# LPEDT_revA1_bikeit_GPS.net
KiCad netlist of a schematic drawn in Altium Designer
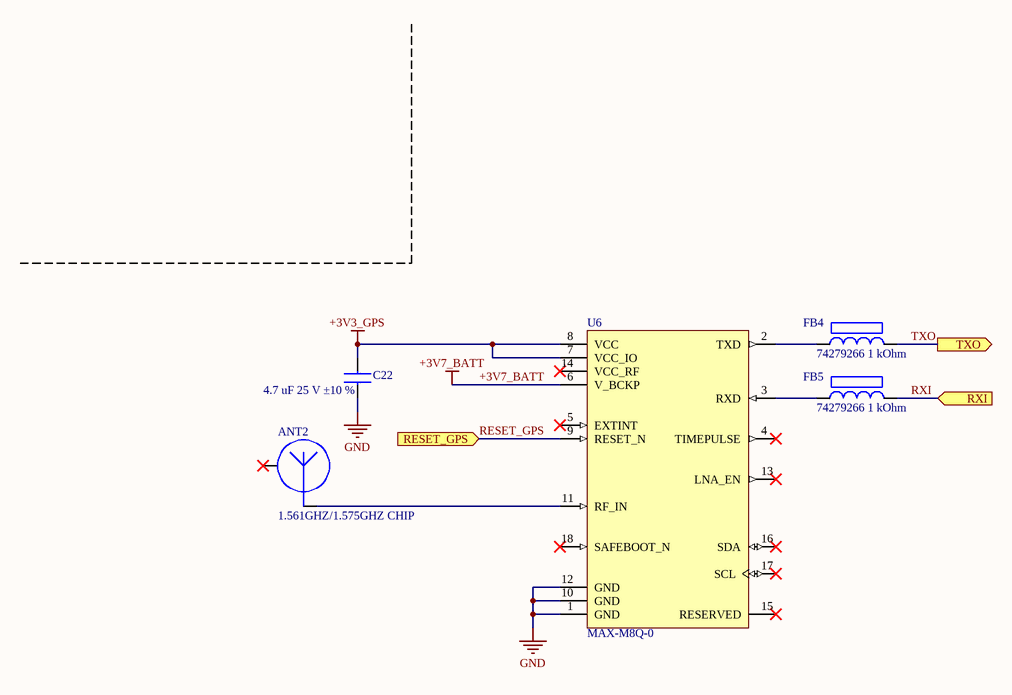
[diagram p0: LPEDT_revA1_bikeit_GPS.SchDoc]

(export (version "E")
  (design (tool "Eeschema 10.0.6"))
  (components
    (comp (ref "ANT2")
      (value "1.561GHZ/1.575GHZ CHIP")
      (description "RF ANT 1.561GHZ/1.575GHZ CHIP")
      (fields
        (field (name "MANUFACTURER") "Johanson")
        (field (name "MANUFACTURER PART NUMBER") "1575AT43A0040E")
      )
      (libsource (lib "LPEDT_revA1_bikeit_IL") (part "1575AT43A0040E"))
    )
    (comp (ref "C22")
      (value "4.7 uF 25 V ±10 %")
      (footprint "CAP_0603_1.60mm*0.80mm")
      (description "Cap Ceramic 0603 4.7 uF 25 V ±10 % Tolerance X5R SMT Multilayer Ceramic Capacitor")
      (fields
        (field (name "MANUFACTURER") "Murata")
        (field (name "MANUFACTURER PART NUMBER") "GRM188R61E475KE11D")
      )
      (libsource (lib "LPEDT_revA1_bikeit_IL") (part "GRM188R61E475KE11D"))
    )
    (comp (ref "FB4")
      (value "74279266 1 kOhm")
      (footprint "FB_0603_1.60mm*0.80mm")
      (description "Ferrite Bead, 0603 [1608 Metric], 1 kohm, 200 mA, WE-CBF Series, 0.6 ohm, ± 25%")
      (fields
        (field (name "MANUFACTURER") "Wurth Electronics")
        (field (name "MANUFACTURER PART NUMBER") "74279266")
      )
      (libsource (lib "LPEDT_revA1_bikeit_IL") (part "74279266"))
    )
    (comp (ref "FB5")
      (value "74279266 1 kOhm")
      (footprint "FB_0603_1.60mm*0.80mm")
      (description "Ferrite Bead, 0603 [1608 Metric], 1 kohm, 200 mA, WE-CBF Series, 0.6 ohm, ± 25%")
      (fields
        (field (name "MANUFACTURER") "Wurth Electronics")
        (field (name "MANUFACTURER PART NUMBER") "74279266")
      )
      (libsource (lib "LPEDT_revA1_bikeit_IL") (part "74279266"))
    )
    (comp (ref "U6")
      (value "MAX-M8Q-0")
      (footprint "XCVR_MAX-M8C-0-10")
      (description "MAX-M8 RF Receiver BeiDou, Galileo, GLONASS, GNSS, GPS 1.575GHz -167dBm")
      (fields (field (name "MF") "U-Blox America"))
      (libsource (lib "LPEDT_revA1_bikeit") (part "MAX-M8Q-0"))
    )
  )
  (nets
    (net (code "1") (name "+3V3_GPS") (class "Default")
      (node (ref "C22") (pin "1") (pinfunction "1_1") (pintype "passive"))
      (node (ref "U6") (pin "7") (pinfunction "VCC_IO_7") (pintype "power_in"))
      (node (ref "U6") (pin "8") (pinfunction "VCC_8") (pintype "power_in"))
    )
    (net (code "2") (name "+3V7_BATT") (class "Default")
      (node (ref "U6") (pin "6") (pinfunction "V_BCKP_6") (pintype "power_in"))
    )
    (net (code "3") (name "/RESET_GPS") (class "Default")
      (node (ref "U6") (pin "9") (pinfunction "RESET_N_9") (pintype "input"))
    )
    (net (code "4") (name "/RXI") (class "Default")
      (node (ref "FB5") (pin "2") (pinfunction "2_2") (pintype "passive"))
    )
    (net (code "5") (name "/TXO") (class "Default")
      (node (ref "FB4") (pin "2") (pinfunction "2_2") (pintype "passive"))
    )
    (net (code "6") (name "GND") (class "Default")
      (node (ref "C22") (pin "2") (pinfunction "2_2") (pintype "passive"))
      (node (ref "U6") (pin "1") (pinfunction "GND_1") (pintype "passive"))
      (node (ref "U6") (pin "10") (pinfunction "GND_10") (pintype "passive"))
      (node (ref "U6") (pin "12") (pinfunction "GND_12") (pintype "passive"))
    )
    (net (code "7") (name "Net-(ANT2-FEED)") (class "Default")
      (node (ref "ANT2") (pin "1") (pinfunction "FEED_1") (pintype "passive"))
      (node (ref "U6") (pin "11") (pinfunction "RF_IN_11") (pintype "input"))
    )
    (net (code "8") (name "Net-(U6-RXD)") (class "Default")
      (node (ref "FB5") (pin "1") (pinfunction "1_1") (pintype "passive"))
      (node (ref "U6") (pin "3") (pinfunction "RXD_3") (pintype "input"))
    )
    (net (code "9") (name "Net-(U6-TXD)") (class "Default")
      (node (ref "FB4") (pin "1") (pinfunction "1_1") (pintype "passive"))
      (node (ref "U6") (pin "2") (pinfunction "TXD_2") (pintype "output"))
    )
    (net (code "10") (name "unconnected-(ANT2-NC-Pad2)") (class "Default")
      (node (ref "ANT2") (pin "2") (pinfunction "NC_2") (pintype "passive+no_connect"))
    )
    (net (code "11") (name "unconnected-(U6-EXTINT-Pad5)") (class "Default")
      (node (ref "U6") (pin "5") (pinfunction "EXTINT_5") (pintype "input+no_connect"))
    )
    (net (code "12") (name "unconnected-(U6-LNA_EN-Pad13)") (class "Default")
      (node (ref "U6") (pin "13") (pinfunction "LNA_EN_13") (pintype "output+no_connect"))
    )
    (net (code "13") (name "unconnected-(U6-RESERVED-Pad15)") (class "Default")
      (node (ref "U6") (pin "15") (pinfunction "RESERVED_15") (pintype "tri_state+no_connect"))
    )
    (net (code "14") (name "unconnected-(U6-SAFEBOOT_N-Pad18)") (class "Default")
      (node (ref "U6") (pin "18") (pinfunction "SAFEBOOT_N_18") (pintype "input+no_connect"))
    )
    (net (code "15") (name "unconnected-(U6-SCL-Pad17)") (class "Default")
      (node (ref "U6") (pin "17") (pinfunction "SCL_17") (pintype "bidirectional+no_connect"))
    )
    (net (code "16") (name "unconnected-(U6-SDA-Pad16)") (class "Default")
      (node (ref "U6") (pin "16") (pinfunction "SDA_16") (pintype "bidirectional+no_connect"))
    )
    (net (code "17") (name "unconnected-(U6-TIMEPULSE-Pad4)") (class "Default")
      (node (ref "U6") (pin "4") (pinfunction "TIMEPULSE_4") (pintype "output+no_connect"))
    )
    (net (code "18") (name "unconnected-(U6-VCC_RF-Pad14)") (class "Default")
      (node (ref "U6") (pin "14") (pinfunction "VCC_RF_14") (pintype "power_in+no_connect"))
    )
  )
)
